# MCU063A_Emulator.net
KiCad netlist of a schematic drawn in Altium Designer
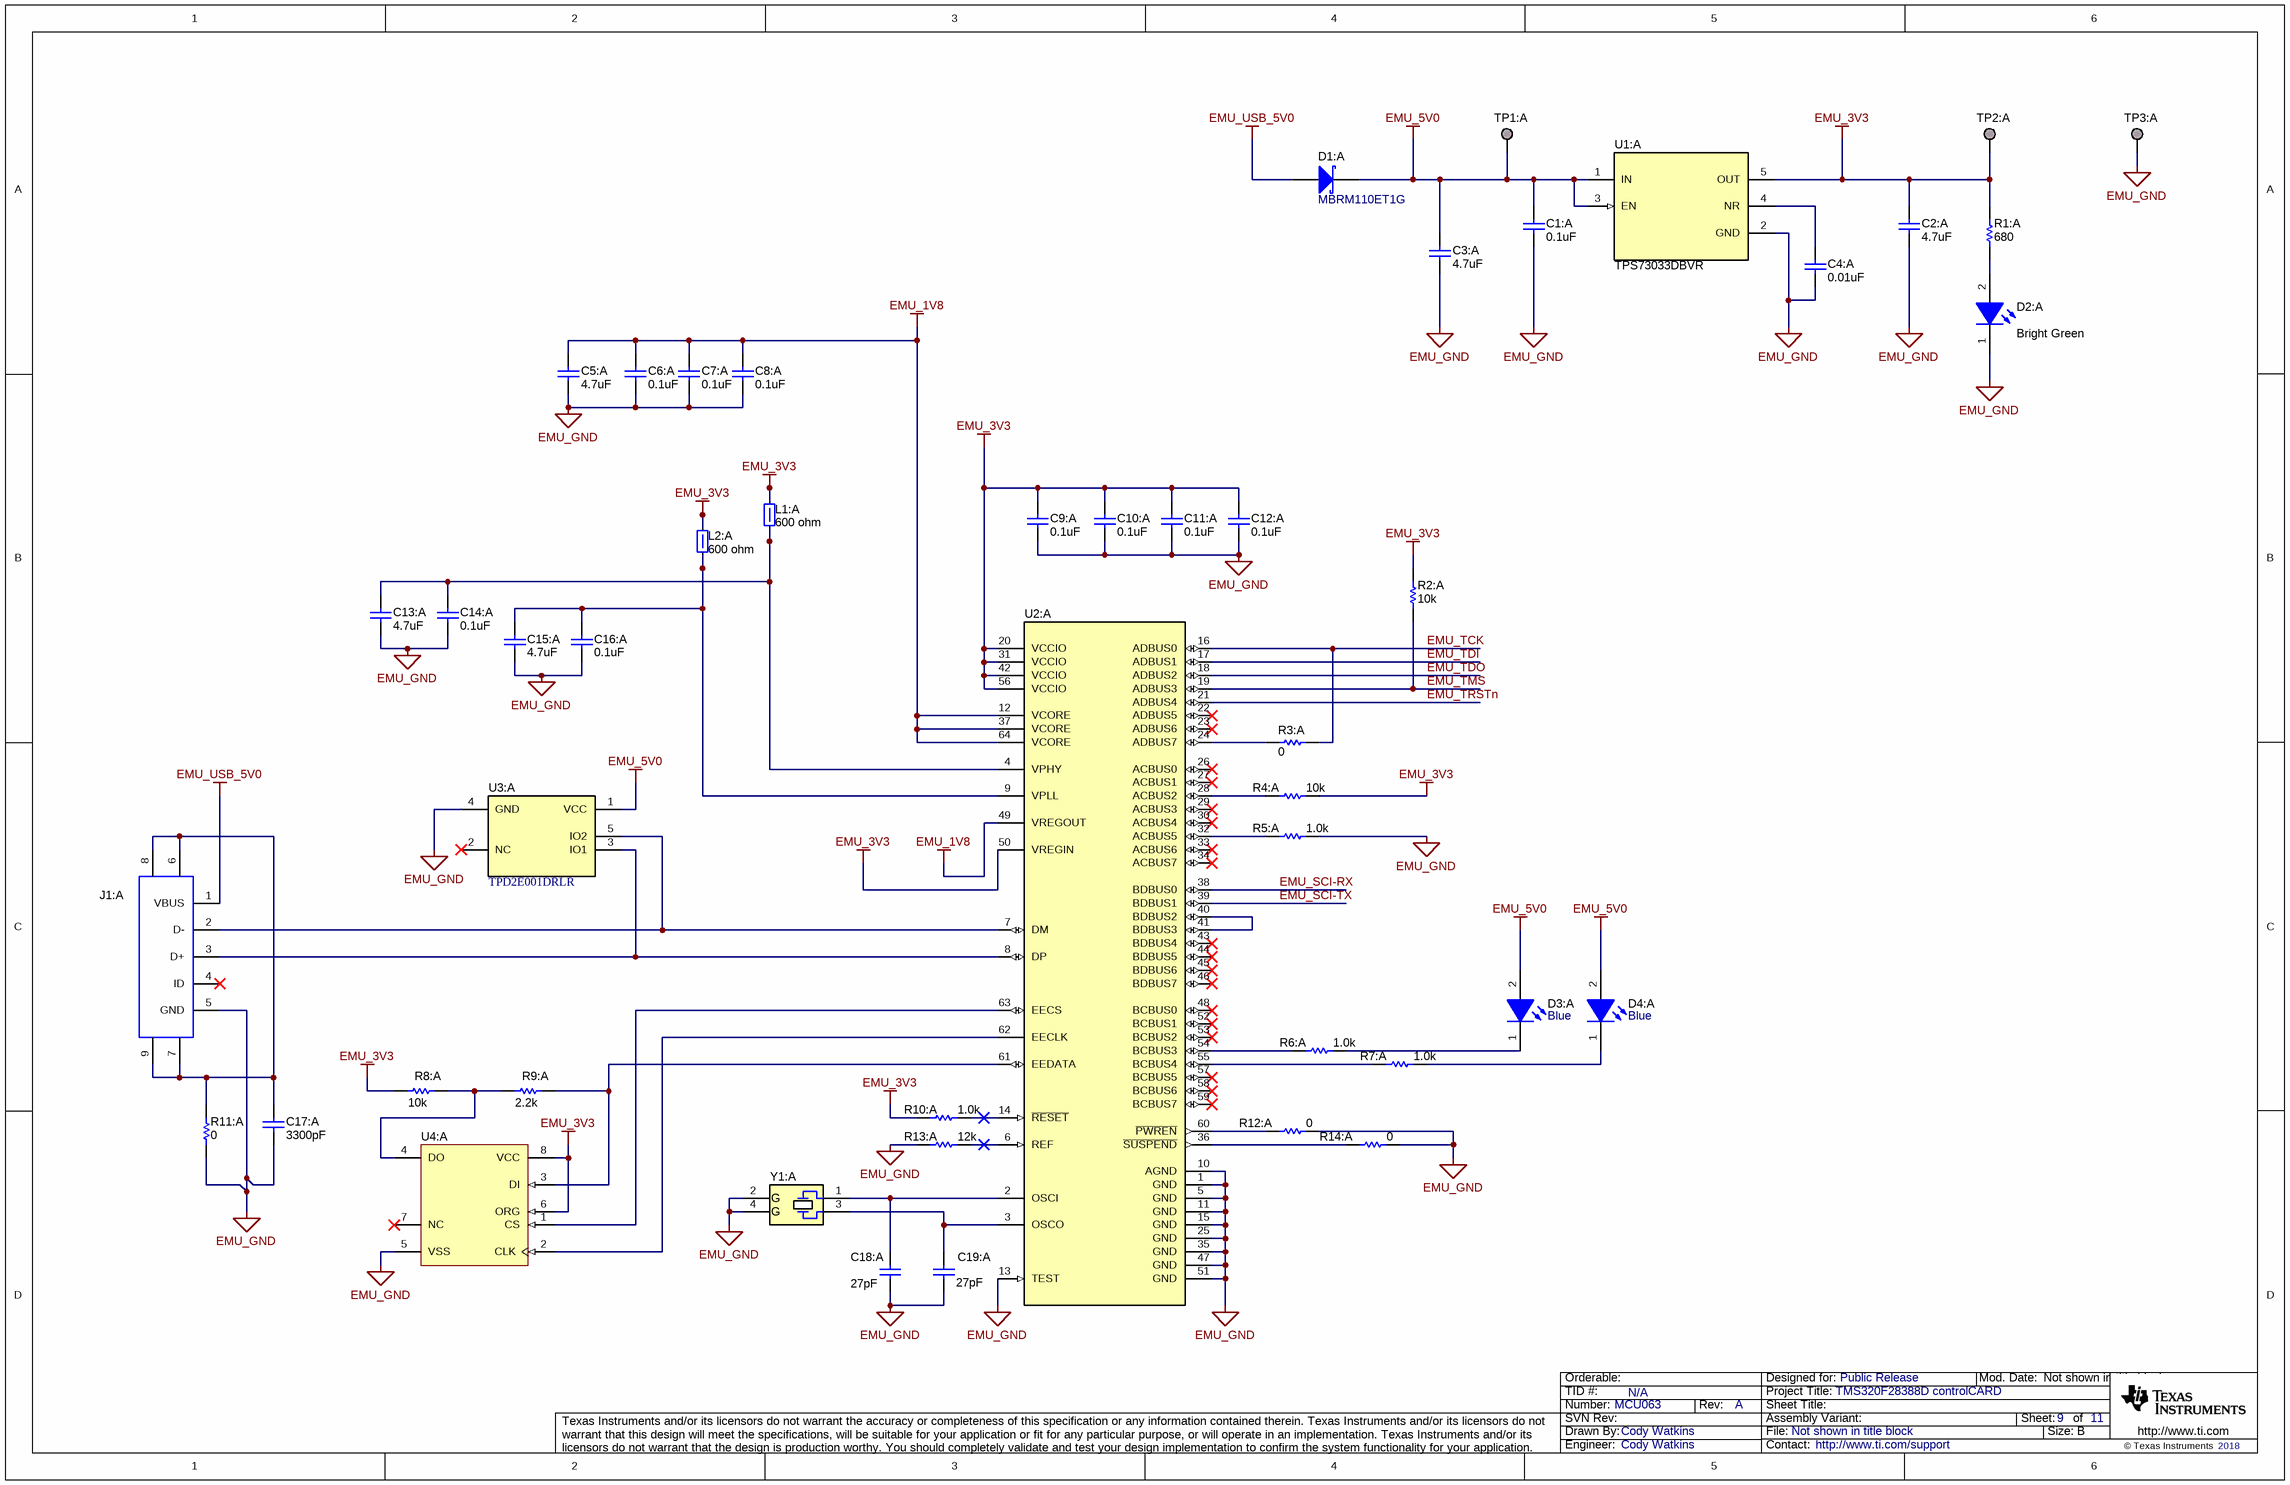
[diagram p0: MCU063A_Emulator.SchDoc]

(export (version "E")
  (design (tool "Eeschema 10.0.6"))
  (components
    (comp (ref "C1:A")
      (value "CL05B104KP5NNNC")
      (footprint "0402")
      (description "CAP, CERM, 0.1 uF, 10 V, +/- 10%, X7R, 0402")
      (fields
        (field (name "VALUEDISPLAYED") "0.1uF")
        (field (name "MANUFACTURER") "Samsung Electro-Mechanics")
        (field (name "PUBLISHER") "Texas Instruments")
      )
      (libsource (lib "Altium Vault - TI") (part "Capacitor"))
    )
    (comp (ref "C2:A")
      (value "C0603C475K9PACTU")
      (footprint "0603")
      (description "CAP, CERM, 4.7 uF, 6.3 V, +/- 10%, X5R, 0603")
      (fields
        (field (name "MANUFACTURER") "Kemet")
        (field (name "VALUEDISPLAYED") "4.7uF")
        (field (name "PUBLISHER") "Texas Instruments")
      )
      (libsource (lib "Altium Vault - TI") (part "Capacitor"))
    )
    (comp (ref "C3:A")
      (value "C0603C475K9PACTU")
      (footprint "0603")
      (description "CAP, CERM, 4.7 uF, 6.3 V, +/- 10%, X5R, 0603")
      (fields
        (field (name "MANUFACTURER") "Kemet")
        (field (name "VALUEDISPLAYED") "4.7uF")
        (field (name "PUBLISHER") "Texas Instruments")
      )
      (libsource (lib "Altium Vault - TI") (part "Capacitor"))
    )
    (comp (ref "C4:A")
      (value "0402ZC103KAT2A")
      (footprint "0402")
      (description "CAP, CERM, 0.01 uF, 10 V, +/- 10%, X7R, 0402")
      (fields
        (field (name "VALUEDISPLAYED") "0.01uF")
        (field (name "MANUFACTURER") "AVX")
        (field (name "PUBLISHER") "Texas Instruments")
      )
      (libsource (lib "Altium Vault - TI") (part "Capacitor"))
    )
    (comp (ref "C5:A")
      (value "C0603C475K9PACTU")
      (footprint "0603")
      (description "CAP, CERM, 4.7 uF, 6.3 V, +/- 10%, X5R, 0603")
      (fields
        (field (name "MANUFACTURER") "Kemet")
        (field (name "VALUEDISPLAYED") "4.7uF")
        (field (name "PUBLISHER") "Texas Instruments")
      )
      (libsource (lib "Altium Vault - TI") (part "Capacitor"))
    )
    (comp (ref "C6:A")
      (value "CL05B104KP5NNNC")
      (footprint "0402")
      (description "CAP, CERM, 0.1 uF, 10 V, +/- 10%, X7R, 0402")
      (fields
        (field (name "VALUEDISPLAYED") "0.1uF")
        (field (name "MANUFACTURER") "Samsung Electro-Mechanics")
        (field (name "PUBLISHER") "Texas Instruments")
      )
      (libsource (lib "Altium Vault - TI") (part "Capacitor"))
    )
    (comp (ref "C7:A")
      (value "CL05B104KP5NNNC")
      (footprint "0402")
      (description "CAP, CERM, 0.1 uF, 10 V, +/- 10%, X7R, 0402")
      (fields
        (field (name "VALUEDISPLAYED") "0.1uF")
        (field (name "MANUFACTURER") "Samsung Electro-Mechanics")
        (field (name "PUBLISHER") "Texas Instruments")
      )
      (libsource (lib "Altium Vault - TI") (part "Capacitor"))
    )
    (comp (ref "C8:A")
      (value "CL05B104KP5NNNC")
      (footprint "0402")
      (description "CAP, CERM, 0.1 uF, 10 V, +/- 10%, X7R, 0402")
      (fields
        (field (name "VALUEDISPLAYED") "0.1uF")
        (field (name "MANUFACTURER") "Samsung Electro-Mechanics")
        (field (name "PUBLISHER") "Texas Instruments")
      )
      (libsource (lib "Altium Vault - TI") (part "Capacitor"))
    )
    (comp (ref "C9:A")
      (value "CL05B104KP5NNNC")
      (footprint "0402")
      (description "CAP, CERM, 0.1 uF, 10 V, +/- 10%, X7R, 0402")
      (fields
        (field (name "VALUEDISPLAYED") "0.1uF")
        (field (name "MANUFACTURER") "Samsung Electro-Mechanics")
        (field (name "PUBLISHER") "Texas Instruments")
      )
      (libsource (lib "Altium Vault - TI") (part "Capacitor"))
    )
    (comp (ref "C10:A")
      (value "CL05B104KP5NNNC")
      (footprint "0402")
      (description "CAP, CERM, 0.1 uF, 10 V, +/- 10%, X7R, 0402")
      (fields
        (field (name "VALUEDISPLAYED") "0.1uF")
        (field (name "MANUFACTURER") "Samsung Electro-Mechanics")
        (field (name "PUBLISHER") "Texas Instruments")
      )
      (libsource (lib "Altium Vault - TI") (part "Capacitor"))
    )
    (comp (ref "C11:A")
      (value "CL05B104KP5NNNC")
      (footprint "0402")
      (description "CAP, CERM, 0.1 uF, 10 V, +/- 10%, X7R, 0402")
      (fields
        (field (name "VALUEDISPLAYED") "0.1uF")
        (field (name "MANUFACTURER") "Samsung Electro-Mechanics")
        (field (name "PUBLISHER") "Texas Instruments")
      )
      (libsource (lib "Altium Vault - TI") (part "Capacitor"))
    )
    (comp (ref "C12:A")
      (value "CL05B104KP5NNNC")
      (footprint "0402")
      (description "CAP, CERM, 0.1 uF, 10 V, +/- 10%, X7R, 0402")
      (fields
        (field (name "VALUEDISPLAYED") "0.1uF")
        (field (name "MANUFACTURER") "Samsung Electro-Mechanics")
        (field (name "PUBLISHER") "Texas Instruments")
      )
      (libsource (lib "Altium Vault - TI") (part "Capacitor"))
    )
    (comp (ref "C13:A")
      (value "C0603C475K9PACTU")
      (footprint "0603")
      (description "CAP, CERM, 4.7 uF, 6.3 V, +/- 10%, X5R, 0603")
      (fields
        (field (name "MANUFACTURER") "Kemet")
        (field (name "VALUEDISPLAYED") "4.7uF")
        (field (name "PUBLISHER") "Texas Instruments")
      )
      (libsource (lib "Altium Vault - TI") (part "Capacitor"))
    )
    (comp (ref "C14:A")
      (value "CL05B104KP5NNNC")
      (footprint "0402")
      (description "CAP, CERM, 0.1 uF, 10 V, +/- 10%, X7R, 0402")
      (fields
        (field (name "VALUEDISPLAYED") "0.1uF")
        (field (name "MANUFACTURER") "Samsung Electro-Mechanics")
        (field (name "PUBLISHER") "Texas Instruments")
      )
      (libsource (lib "Altium Vault - TI") (part "Capacitor"))
    )
    (comp (ref "C15:A")
      (value "C0603C475K9PACTU")
      (footprint "0603")
      (description "CAP, CERM, 4.7 uF, 6.3 V, +/- 10%, X5R, 0603")
      (fields
        (field (name "MANUFACTURER") "Kemet")
        (field (name "VALUEDISPLAYED") "4.7uF")
        (field (name "PUBLISHER") "Texas Instruments")
      )
      (libsource (lib "Altium Vault - TI") (part "Capacitor"))
    )
    (comp (ref "C16:A")
      (value "CL05B104KP5NNNC")
      (footprint "0402")
      (description "CAP, CERM, 0.1 uF, 10 V, +/- 10%, X7R, 0402")
      (fields
        (field (name "VALUEDISPLAYED") "0.1uF")
        (field (name "MANUFACTURER") "Samsung Electro-Mechanics")
        (field (name "PUBLISHER") "Texas Instruments")
      )
      (libsource (lib "Altium Vault - TI") (part "Capacitor"))
    )
    (comp (ref "C17:A")
      (value "CGA2B2X7R1H332K050BA")
      (footprint "0402")
      (description "CAP, CERM, 3300 pF, 50 V, +/- 10%, X7R, AEC-Q200 Grade 1, 0402")
      (fields
        (field (name "MANUFACTURER") "TDK")
        (field (name "VALUEDISPLAYED") "3300pF")
        (field (name "PUBLISHER") "Texas Instruments")
      )
      (libsource (lib "Altium Vault - TI") (part "Capacitor"))
    )
    (comp (ref "C18:A")
      (value "C0402C270J5GACTU")
      (footprint "0402")
      (description "CAP, CERM, 27 pF, 50 V,+/- 5%, C0G/NP0, 0402")
      (fields (field (name "VALUEDISPLAYED") "27pF") (field (name "MANUFACTURER") "Kemet"))
      (libsource (lib "Altium Vault - TI") (part "Capacitor"))
    )
    (comp (ref "C19:A")
      (value "C0402C270J5GACTU")
      (footprint "0402")
      (description "CAP, CERM, 27 pF, 50 V,+/- 5%, C0G/NP0, 0402")
      (fields (field (name "VALUEDISPLAYED") "27pF") (field (name "MANUFACTURER") "Kemet"))
      (libsource (lib "Altium Vault - TI") (part "Capacitor"))
    )
    (comp (ref "D1:A")
      (value "MBRM110ET1G")
      (footprint "POWERMITE")
      (description "Diode, Schottky, 10 V, 1 A, AEC-Q101, POWERMITE")
      (fields (field (name "MANUFACTURER") "ON Semiconductor"))
      (libsource (lib "Altium Vault - TI") (part "DIODE_SCHOTTKY"))
    )
    (comp (ref "D2:A")
      (value "Bright Green")
      (footprint "WL-SMCW_Green_0805")
      (description "LED, Bright Green, SMD")
      (fields
        (field (name "PARTNUMBER") "150080VS75000")
        (field (name "MANUFACTURER") "Wurth Elektronik")
        (field (name "PUBLISHER") "Texas Instruments")
      )
      (libsource (lib "Altium Vault - TI") (part "LED_A2_K1"))
    )
    (comp (ref "D3:A")
      (value "Blue")
      (footprint "WL-SMCW_Blue_0805")
      (description "LED, Blue, SMD")
      (fields (field (name "MANUFACTURER") "Wurth Elektronik") (field (name "PARTNUMBER") "150080BS75000"))
      (libsource (lib "Altium Vault - TI") (part "LED_A2_K1"))
    )
    (comp (ref "D4:A")
      (value "Blue")
      (footprint "WL-SMCW_Blue_0805")
      (description "LED, Blue, SMD")
      (fields (field (name "MANUFACTURER") "Wurth Elektronik") (field (name "PARTNUMBER") "150080BS75000"))
      (libsource (lib "Altium Vault - TI") (part "LED_A2_K1"))
    )
    (comp (ref "J1:A")
      (value "65100516121")
      (footprint "Wurth_65100516121")
      (description "Connector, Receptacle, USB Mini B 2.0, SMT")
      (fields (field (name "MANUFACTURER") "Wurth Elektronik") (field (name "PUBLISHER") "Texas Instruments"))
      (libsource (lib "Altium Vault - TI") (part "CONN_USB_5Pos-4Shld"))
    )
    (comp (ref "L1:A")
      (value "600 ohm")
      (footprint "0805_HV")
      (description "Ferrite Bead, 600 ohm @ 100 MHz, 0.5 A, 0805")
      (fields
        (field (name "PARTNUMBER") "HZ0805E601R-10")
        (field (name "MANUFACTURER") "Laird-Signal Integrity Products")
        (field (name "PUBLISHER") "Texas Instruments")
      )
      (libsource (lib "Altium Vault - TI") (part "Ferrite_Bead"))
    )
    (comp (ref "L2:A")
      (value "600 ohm")
      (footprint "0805_HV")
      (description "Ferrite Bead, 600 ohm @ 100 MHz, 0.5 A, 0805")
      (fields
        (field (name "PARTNUMBER") "HZ0805E601R-10")
        (field (name "MANUFACTURER") "Laird-Signal Integrity Products")
        (field (name "PUBLISHER") "Texas Instruments")
      )
      (libsource (lib "Altium Vault - TI") (part "Ferrite_Bead"))
    )
    (comp (ref "R1:A")
      (value "CRCW0402680RJNED")
      (footprint "0402")
      (description "RES, 680, 5%, 0.063 W, AEC-Q200 Grade 0, 0402")
      (fields (field (name "VALUEDISPLAYED") "680") (field (name "MANUFACTURER") "Vishay-Dale"))
      (libsource (lib "Altium Vault - TI") (part "Resistor"))
    )
    (comp (ref "R2:A")
      (value "CRCW040210K0JNED")
      (footprint "0402")
      (description "RES, 10 k, 5%, 0.063 W, AEC-Q200 Grade 0, 0402")
      (fields (field (name "VALUEDISPLAYED") "10k") (field (name "MANUFACTURER") "Vishay-Dale"))
      (libsource (lib "Altium Vault - TI") (part "Resistor"))
    )
    (comp (ref "R3:A")
      (value "CRCW04020000Z0ED")
      (footprint "0402")
      (description "RES, 0, 5%, 0.063 W, AEC-Q200 Grade 0, 0402")
      (fields (field (name "VALUEDISPLAYED") "0") (field (name "MANUFACTURER") "Vishay-Dale"))
      (libsource (lib "Altium Vault - TI") (part "Resistor"))
    )
    (comp (ref "R4:A")
      (value "CRCW040210K0JNED")
      (footprint "0402")
      (description "RES, 10 k, 5%, 0.063 W, AEC-Q200 Grade 0, 0402")
      (fields (field (name "VALUEDISPLAYED") "10k") (field (name "MANUFACTURER") "Vishay-Dale"))
      (libsource (lib "Altium Vault - TI") (part "Resistor"))
    )
    (comp (ref "R5:A")
      (value "CRCW04021K00JNED")
      (footprint "0402")
      (description "RES, 1.0 k, 5%, 0.063 W, AEC-Q200 Grade 0, 0402")
      (fields (field (name "VALUEDISPLAYED") "1.0k") (field (name "MANUFACTURER") "Vishay-Dale"))
      (libsource (lib "Altium Vault - TI") (part "Resistor"))
    )
    (comp (ref "R6:A")
      (value "CRCW04021K00JNED")
      (footprint "0402")
      (description "RES, 1.0 k, 5%, 0.063 W, AEC-Q200 Grade 0, 0402")
      (fields (field (name "VALUEDISPLAYED") "1.0k") (field (name "MANUFACTURER") "Vishay-Dale"))
      (libsource (lib "Altium Vault - TI") (part "Resistor"))
    )
    (comp (ref "R7:A")
      (value "CRCW04021K00JNED")
      (footprint "0402")
      (description "RES, 1.0 k, 5%, 0.063 W, AEC-Q200 Grade 0, 0402")
      (fields (field (name "VALUEDISPLAYED") "1.0k") (field (name "MANUFACTURER") "Vishay-Dale"))
      (libsource (lib "Altium Vault - TI") (part "Resistor"))
    )
    (comp (ref "R8:A")
      (value "CRCW040210K0JNED")
      (footprint "0402")
      (description "RES, 10 k, 5%, 0.063 W, AEC-Q200 Grade 0, 0402")
      (fields (field (name "VALUEDISPLAYED") "10k") (field (name "MANUFACTURER") "Vishay-Dale"))
      (libsource (lib "Altium Vault - TI") (part "Resistor"))
    )
    (comp (ref "R9:A")
      (value "CRCW04022K20JNED")
      (footprint "0402")
      (description "RES, 2.2 k, 5%, 0.063 W, AEC-Q200 Grade 0, 0402")
      (fields (field (name "VALUEDISPLAYED") "2.2k") (field (name "MANUFACTURER") "Vishay-Dale"))
      (libsource (lib "Altium Vault - TI") (part "Resistor"))
    )
    (comp (ref "R10:A")
      (value "CRCW04021K00JNED")
      (footprint "0402")
      (description "RES, 1.0 k, 5%, 0.063 W, AEC-Q200 Grade 0, 0402")
      (fields (field (name "VALUEDISPLAYED") "1.0k") (field (name "MANUFACTURER") "Vishay-Dale"))
      (libsource (lib "Altium Vault - TI") (part "Resistor"))
    )
    (comp (ref "R11:A")
      (value "CRCW04020000Z0ED")
      (footprint "0402")
      (description "RES, 0, 5%, 0.063 W, AEC-Q200 Grade 0, 0402")
      (fields (field (name "VALUEDISPLAYED") "0") (field (name "MANUFACTURER") "Vishay-Dale"))
      (libsource (lib "Altium Vault - TI") (part "Resistor"))
    )
    (comp (ref "R12:A")
      (value "CRCW04020000Z0ED")
      (footprint "0402")
      (description "RES, 0, 5%, 0.063 W, AEC-Q200 Grade 0, 0402")
      (fields (field (name "VALUEDISPLAYED") "0") (field (name "MANUFACTURER") "Vishay-Dale"))
      (libsource (lib "Altium Vault - TI") (part "Resistor"))
    )
    (comp (ref "R13:A")
      (value "CRCW040212K0JNED")
      (footprint "0402")
      (description "RES, 12 k, 5%, 0.063 W, AEC-Q200 Grade 0, 0402")
      (fields (field (name "VALUEDISPLAYED") "12k") (field (name "MANUFACTURER") "Vishay-Dale"))
      (libsource (lib "Altium Vault - TI") (part "Resistor"))
    )
    (comp (ref "R14:A")
      (value "CRCW04020000Z0ED")
      (footprint "0402")
      (description "RES, 0, 5%, 0.063 W, AEC-Q200 Grade 0, 0402")
      (fields (field (name "VALUEDISPLAYED") "0") (field (name "MANUFACTURER") "Vishay-Dale"))
      (libsource (lib "Altium Vault - TI") (part "Resistor"))
    )
    (comp (ref "TP1:A")
      (value "TESTPOINT")
      (footprint "TP_50MIL-25MILHOLE")
      (description "TEST POINT.  No entry in BOM.")
      (libsource (lib "Altium Vault - TI") (part "CMP-0078143-2"))
    )
    (comp (ref "TP2:A")
      (value "TESTPOINT")
      (footprint "TP_50MIL-25MILHOLE")
      (description "TEST POINT.  No entry in BOM.")
      (libsource (lib "Altium Vault - TI") (part "CMP-0078143-2"))
    )
    (comp (ref "TP3:A")
      (value "TESTPOINT")
      (footprint "TP_50MIL-25MILHOLE")
      (description "TEST POINT.  No entry in BOM.")
      (libsource (lib "Altium Vault - TI") (part "CMP-0078143-2"))
    )
    (comp (ref "U1:A")
      (value "TPS73033DBVR")
      (footprint "DBV0005A_N")
      (description "Low-Noise, High PSRR, RF 200-mA Low-Dropout Linear Regulators, DBV0005A (SOT-23-5)")
      (fields
        (field (name "ALTERNATE PARTNUMBER") "TPS73033DBVT")
        (field (name "MANUFACTURER") "Texas Instruments")
        (field (name "PUBLISHER") "Texas Instruments")
      )
      (libsource (lib "Altium Vault - TI") (part "TPS730XXDBV"))
    )
    (comp (ref "U2:A")
      (value "FT2232HL-REEL")
      (footprint "LQFP64_N")
      (description "Dual High Speed USB To Multipurpose UART/FIFO IC, LQFP-64")
      (fields (field (name "MANUFACTURER") "FTDI") (field (name "PUBLISHER") "Texas Instruments"))
      (libsource (lib "Altium Vault - TI") (part "CMP-0004796-1"))
    )
    (comp (ref "U3:A")
      (value "TPD2E001DRLR")
      (footprint "DRL0005A")
      (fields (field (name "MANUFACTURER") "Texas Instruments"))
      (libsource (lib "Altium Vault - TI") (part "TI-TPD2E001-Q1-SOT_DRL-5"))
    )
    (comp (ref "U4:A")
      (value "93LC56C-I/SN")
      (footprint "SOIC-8")
      (description "2K Microwire Compatible Serial EEPROM, SOIC-8")
      (fields (field (name "MANUFACTURER") "Microchip") (field (name "PUBLISHER") "Texas Instruments"))
      (libsource (lib "Altium Vault - TI") (part "93LC46C-SN"))
    )
    (comp (ref "Y1:A")
      (value "ECS-120-20-30B-TR")
      (footprint "ECS_ECX-53B")
      (description "Crystal, 12 MHz, 20pF, SMD")
      (fields (field (name "MANUFACTURER") "ECS Inc."))
      (libsource (lib "Altium Vault - TI") (part "CMP-0004646-3"))
    )
  )
  (nets
    (net (code "1") (name "/EMU_SCI-RX") (class "Default")
      (node (ref "U2:A") (pin "38") (pinfunction "BDBUS0_38") (pintype "bidirectional"))
    )
    (net (code "2") (name "/EMU_SCI-TX") (class "Default")
      (node (ref "U2:A") (pin "39") (pinfunction "BDBUS1_39") (pintype "bidirectional"))
    )
    (net (code "3") (name "/EMU_TCK") (class "Default")
      (node (ref "R3:A") (pin "1") (pinfunction "1_1") (pintype "passive"))
      (node (ref "U2:A") (pin "16") (pinfunction "ADBUS0_16") (pintype "bidirectional"))
    )
    (net (code "4") (name "/EMU_TDI") (class "Default")
      (node (ref "U2:A") (pin "17") (pinfunction "ADBUS1_17") (pintype "bidirectional"))
    )
    (net (code "5") (name "/EMU_TDO") (class "Default")
      (node (ref "U2:A") (pin "18") (pinfunction "ADBUS2_18") (pintype "bidirectional"))
    )
    (net (code "6") (name "/EMU_TMS") (class "Default")
      (node (ref "R2:A") (pin "1") (pinfunction "1_1") (pintype "passive"))
      (node (ref "U2:A") (pin "19") (pinfunction "ADBUS3_19") (pintype "bidirectional"))
    )
    (net (code "7") (name "/EMU_TRSTn") (class "Default")
      (node (ref "U2:A") (pin "21") (pinfunction "ADBUS4_21") (pintype "bidirectional"))
    )
    (net (code "8") (name "EMU_1V8") (class "Default")
      (node (ref "C5:A") (pin "2") (pinfunction "2_2") (pintype "passive"))
      (node (ref "C6:A") (pin "2") (pinfunction "2_2") (pintype "passive"))
      (node (ref "C7:A") (pin "2") (pinfunction "2_2") (pintype "passive"))
      (node (ref "C8:A") (pin "2") (pinfunction "2_2") (pintype "passive"))
      (node (ref "U2:A") (pin "12") (pinfunction "VCORE_12") (pintype "power_in"))
      (node (ref "U2:A") (pin "37") (pinfunction "VCORE_37") (pintype "power_in"))
      (node (ref "U2:A") (pin "49") (pinfunction "VREGOUT_49") (pintype "power_in"))
      (node (ref "U2:A") (pin "64") (pinfunction "VCORE_64") (pintype "power_in"))
    )
    (net (code "9") (name "EMU_3V3") (class "Default")
      (node (ref "C10:A") (pin "2") (pinfunction "2_2") (pintype "passive"))
      (node (ref "C11:A") (pin "2") (pinfunction "2_2") (pintype "passive"))
      (node (ref "C12:A") (pin "2") (pinfunction "2_2") (pintype "passive"))
      (node (ref "C2:A") (pin "1") (pinfunction "1_1") (pintype "passive"))
      (node (ref "C9:A") (pin "2") (pinfunction "2_2") (pintype "passive"))
      (node (ref "L1:A") (pin "2") (pinfunction "2_2") (pintype "passive"))
      (node (ref "L2:A") (pin "2") (pinfunction "2_2") (pintype "passive"))
      (node (ref "R10:A") (pin "1") (pinfunction "1_1") (pintype "passive"))
      (node (ref "R1:A") (pin "1") (pinfunction "1_1") (pintype "passive"))
      (node (ref "R2:A") (pin "2") (pinfunction "2_2") (pintype "passive"))
      (node (ref "R4:A") (pin "2") (pinfunction "2_2") (pintype "passive"))
      (node (ref "R8:A") (pin "1") (pinfunction "1_1") (pintype "passive"))
      (node (ref "TP2:A") (pin "1") (pintype "passive"))
      (node (ref "U1:A") (pin "5") (pinfunction "OUT_5") (pintype "power_in"))
      (node (ref "U2:A") (pin "20") (pinfunction "VCCIO_20") (pintype "power_in"))
      (node (ref "U2:A") (pin "31") (pinfunction "VCCIO_31") (pintype "power_in"))
      (node (ref "U2:A") (pin "42") (pinfunction "VCCIO_42") (pintype "power_in"))
      (node (ref "U2:A") (pin "50") (pinfunction "VREGIN_50") (pintype "power_in"))
      (node (ref "U2:A") (pin "56") (pinfunction "VCCIO_56") (pintype "power_in"))
      (node (ref "U4:A") (pin "6") (pinfunction "ORG_6") (pintype "input"))
      (node (ref "U4:A") (pin "8") (pinfunction "VCC_8") (pintype "power_in"))
    )
    (net (code "10") (name "EMU_5V0") (class "Default")
      (node (ref "C1:A") (pin "2") (pinfunction "2_2") (pintype "passive"))
      (node (ref "C3:A") (pin "1") (pinfunction "1_1") (pintype "passive"))
      (node (ref "D1:A") (pin "1") (pinfunction "K_1") (pintype "passive"))
      (node (ref "D3:A") (pin "2") (pinfunction "A_2") (pintype "passive"))
      (node (ref "D4:A") (pin "2") (pinfunction "A_2") (pintype "passive"))
      (node (ref "TP1:A") (pin "1") (pintype "passive"))
      (node (ref "U1:A") (pin "1") (pinfunction "IN_1") (pintype "power_in"))
      (node (ref "U1:A") (pin "3") (pinfunction "EN_3") (pintype "input"))
      (node (ref "U3:A") (pin "1") (pinfunction "VCC_1") (pintype "power_in"))
    )
    (net (code "11") (name "EMU_GND") (class "Default")
      (node (ref "C10:A") (pin "1") (pinfunction "1_1") (pintype "passive"))
      (node (ref "C11:A") (pin "1") (pinfunction "1_1") (pintype "passive"))
      (node (ref "C12:A") (pin "1") (pinfunction "1_1") (pintype "passive"))
      (node (ref "C13:A") (pin "2") (pinfunction "2_2") (pintype "passive"))
      (node (ref "C14:A") (pin "1") (pinfunction "1_1") (pintype "passive"))
      (node (ref "C15:A") (pin "2") (pinfunction "2_2") (pintype "passive"))
      (node (ref "C16:A") (pin "1") (pinfunction "1_1") (pintype "passive"))
      (node (ref "C17:A") (pin "1") (pinfunction "1_1") (pintype "passive"))
      (node (ref "C18:A") (pin "1") (pinfunction "1_1") (pintype "passive"))
      (node (ref "C19:A") (pin "1") (pinfunction "1_1") (pintype "passive"))
      (node (ref "C1:A") (pin "1") (pinfunction "1_1") (pintype "passive"))
      (node (ref "C2:A") (pin "2") (pinfunction "2_2") (pintype "passive"))
      (node (ref "C3:A") (pin "2") (pinfunction "2_2") (pintype "passive"))
      (node (ref "C4:A") (pin "1") (pinfunction "1_1") (pintype "passive"))
      (node (ref "C5:A") (pin "1") (pinfunction "1_1") (pintype "passive"))
      (node (ref "C6:A") (pin "1") (pinfunction "1_1") (pintype "passive"))
      (node (ref "C7:A") (pin "1") (pinfunction "1_1") (pintype "passive"))
      (node (ref "C8:A") (pin "1") (pinfunction "1_1") (pintype "passive"))
      (node (ref "C9:A") (pin "1") (pinfunction "1_1") (pintype "passive"))
      (node (ref "D2:A") (pin "1") (pinfunction "K_1") (pintype "passive"))
      (node (ref "J1:A") (pin "5") (pinfunction "GND_5") (pintype "passive"))
      (node (ref "R11:A") (pin "2") (pinfunction "2_2") (pintype "passive"))
      (node (ref "R12:A") (pin "1") (pinfunction "1_1") (pintype "passive"))
      (node (ref "R13:A") (pin "1") (pinfunction "1_1") (pintype "passive"))
      (node (ref "R14:A") (pin "1") (pinfunction "1_1") (pintype "passive"))
      (node (ref "R5:A") (pin "2") (pinfunction "2_2") (pintype "passive"))
      (node (ref "TP3:A") (pin "1") (pintype "passive"))
      (node (ref "U1:A") (pin "2") (pinfunction "GND_2") (pintype "power_in"))
      (node (ref "U2:A") (pin "1") (pinfunction "GND_1") (pintype "power_in"))
      (node (ref "U2:A") (pin "10") (pinfunction "AGND_10") (pintype "power_in"))
      (node (ref "U2:A") (pin "11") (pinfunction "GND_11") (pintype "power_in"))
      (node (ref "U2:A") (pin "13") (pinfunction "TEST_13") (pintype "input"))
      (node (ref "U2:A") (pin "15") (pinfunction "GND_15") (pintype "power_in"))
      (node (ref "U2:A") (pin "25") (pinfunction "GND_25") (pintype "power_in"))
      (node (ref "U2:A") (pin "35") (pinfunction "GND_35") (pintype "power_in"))
      (node (ref "U2:A") (pin "47") (pinfunction "GND_47") (pintype "power_in"))
      (node (ref "U2:A") (pin "5") (pinfunction "GND_5") (pintype "power_in"))
      (node (ref "U2:A") (pin "51") (pinfunction "GND_51") (pintype "power_in"))
      (node (ref "U3:A") (pin "4") (pinfunction "GND_4") (pintype "power_in"))
      (node (ref "U4:A") (pin "5") (pinfunction "VSS_5") (pintype "power_in"))
      (node (ref "Y1:A") (pin "2") (pinfunction "GND_2") (pintype "power_in"))
      (node (ref "Y1:A") (pin "4") (pinfunction "GND_4") (pintype "power_in"))
    )
    (net (code "12") (name "EMU_USB_5V0") (class "Default")
      (node (ref "D1:A") (pin "2") (pinfunction "A_2") (pintype "passive"))
      (node (ref "J1:A") (pin "1") (pinfunction "VBUS_1") (pintype "passive"))
    )
    (net (code "13") (name "Net-(C17:A-Pad2)") (class "Default")
      (node (ref "C17:A") (pin "2") (pinfunction "2_2") (pintype "passive"))
      (node (ref "J1:A") (pin "6") (pinfunction "6_6") (pintype "passive"))
      (node (ref "J1:A") (pin "7") (pinfunction "7_7") (pintype "passive"))
      (node (ref "J1:A") (pin "8") (pinfunction "8_8") (pintype "passive"))
      (node (ref "J1:A") (pin "9") (pinfunction "9_9") (pintype "passive"))
      (node (ref "R11:A") (pin "1") (pinfunction "1_1") (pintype "passive"))
    )
    (net (code "14") (name "Net-(D2:A-A)") (class "Default")
      (node (ref "D2:A") (pin "2") (pinfunction "A_2") (pintype "passive"))
      (node (ref "R1:A") (pin "2") (pinfunction "2_2") (pintype "passive"))
    )
    (net (code "15") (name "Net-(D3:A-K)") (class "Default")
      (node (ref "D3:A") (pin "1") (pinfunction "K_1") (pintype "passive"))
      (node (ref "R6:A") (pin "2") (pinfunction "2_2") (pintype "passive"))
    )
    (net (code "16") (name "Net-(D4:A-K)") (class "Default")
      (node (ref "D4:A") (pin "1") (pinfunction "K_1") (pintype "passive"))
      (node (ref "R7:A") (pin "2") (pinfunction "2_2") (pintype "passive"))
    )
    (net (code "17") (name "Net-(J1:A-D+)") (class "Default")
      (node (ref "J1:A") (pin "3") (pinfunction "D+_3") (pintype "passive"))
      (node (ref "U2:A") (pin "8") (pinfunction "DP_8") (pintype "bidirectional"))
      (node (ref "U3:A") (pin "3") (pinfunction "IO1_3") (pintype "passive"))
    )
    (net (code "18") (name "Net-(J1:A-D-)") (class "Default")
      (node (ref "J1:A") (pin "2") (pinfunction "D-_2") (pintype "passive"))
      (node (ref "U2:A") (pin "7") (pinfunction "DM_7") (pintype "bidirectional"))
      (node (ref "U3:A") (pin "5") (pinfunction "IO2_5") (pintype "passive"))
    )
    (net (code "19") (name "Net-(U1:A-NR)") (class "Default")
      (node (ref "C4:A") (pin "2") (pinfunction "2_2") (pintype "passive"))
      (node (ref "U1:A") (pin "4") (pinfunction "NR_4") (pintype "passive"))
    )
    (net (code "20") (name "Net-(U2:A-ACBUS2)") (class "Default")
      (node (ref "R4:A") (pin "1") (pinfunction "1_1") (pintype "passive"))
      (node (ref "U2:A") (pin "28") (pinfunction "ACBUS2_28") (pintype "bidirectional"))
    )
    (net (code "21") (name "Net-(U2:A-ACBUS5)") (class "Default")
      (node (ref "R5:A") (pin "1") (pinfunction "1_1") (pintype "passive"))
      (node (ref "U2:A") (pin "32") (pinfunction "ACBUS5_32") (pintype "bidirectional"))
    )
    (net (code "22") (name "Net-(U2:A-ADBUS7)") (class "Default")
      (node (ref "R3:A") (pin "2") (pinfunction "2_2") (pintype "passive"))
      (node (ref "U2:A") (pin "24") (pinfunction "ADBUS7_24") (pintype "bidirectional"))
    )
    (net (code "23") (name "Net-(U2:A-BCBUS3)") (class "Default")
      (node (ref "R6:A") (pin "1") (pinfunction "1_1") (pintype "passive"))
      (node (ref "U2:A") (pin "54") (pinfunction "BCBUS3_54") (pintype "bidirectional"))
    )
    (net (code "24") (name "Net-(U2:A-BCBUS4)") (class "Default")
      (node (ref "R7:A") (pin "1") (pinfunction "1_1") (pintype "passive"))
      (node (ref "U2:A") (pin "55") (pinfunction "BCBUS4_55") (pintype "bidirectional"))
    )
    (net (code "25") (name "Net-(U2:A-BDBUS2)") (class "Default")
      (node (ref "U2:A") (pin "40") (pinfunction "BDBUS2_40") (pintype "bidirectional"))
      (node (ref "U2:A") (pin "41") (pinfunction "BDBUS3_41") (pintype "bidirectional"))
    )
    (net (code "26") (name "Net-(U2:A-EECLK)") (class "Default")
      (node (ref "U2:A") (pin "62") (pinfunction "EECLK_62") (pintype "tri_state"))
      (node (ref "U4:A") (pin "2") (pinfunction "CLK_2") (pintype "input"))
    )
    (net (code "27") (name "Net-(U2:A-EECS)") (class "Default")
      (node (ref "U2:A") (pin "63") (pinfunction "EECS_63") (pintype "bidirectional"))
      (node (ref "U4:A") (pin "1") (pinfunction "CS_1") (pintype "input"))
    )
    (net (code "28") (name "Net-(U2:A-EEDATA)") (class "Default")
      (node (ref "R9:A") (pin "2") (pinfunction "2_2") (pintype "passive"))
      (node (ref "U2:A") (pin "61") (pinfunction "EEDATA_61") (pintype "bidirectional"))
      (node (ref "U4:A") (pin "3") (pinfunction "DI_3") (pintype "input"))
    )
    (net (code "29") (name "Net-(U2:A-OSCI)") (class "Default")
      (node (ref "C18:A") (pin "2") (pinfunction "2_2") (pintype "passive"))
      (node (ref "U2:A") (pin "2") (pinfunction "OSCI_2") (pintype "passive"))
      (node (ref "Y1:A") (pin "1") (pinfunction "1_1") (pintype "passive"))
    )
    (net (code "30") (name "Net-(U2:A-OSCO)") (class "Default")
      (node (ref "C19:A") (pin "2") (pinfunction "2_2") (pintype "passive"))
      (node (ref "U2:A") (pin "3") (pinfunction "OSCO_3") (pintype "passive"))
      (node (ref "Y1:A") (pin "3") (pinfunction "3_3") (pintype "passive"))
    )
    (net (code "31") (name "Net-(U2:A-REF)") (class "Default")
      (node (ref "R13:A") (pin "2") (pinfunction "2_2") (pintype "passive"))
      (node (ref "U2:A") (pin "6") (pinfunction "REF_6") (pintype "input"))
    )
    (net (code "32") (name "Net-(U2:A-VPHY)") (class "Default")
      (node (ref "C13:A") (pin "1") (pinfunction "1_1") (pintype "passive"))
      (node (ref "C14:A") (pin "2") (pinfunction "2_2") (pintype "passive"))
      (node (ref "L1:A") (pin "1") (pinfunction "1_1") (pintype "passive"))
      (node (ref "U2:A") (pin "4") (pinfunction "VPHY_4") (pintype "power_in"))
    )
    (net (code "33") (name "Net-(U2:A-VPLL)") (class "Default")
      (node (ref "C15:A") (pin "1") (pinfunction "1_1") (pintype "passive"))
      (node (ref "C16:A") (pin "2") (pinfunction "2_2") (pintype "passive"))
      (node (ref "L2:A") (pin "1") (pinfunction "1_1") (pintype "passive"))
      (node (ref "U2:A") (pin "9") (pinfunction "VPLL_9") (pintype "power_in"))
    )
    (net (code "34") (name "Net-(U2:A-~{PWREN})") (class "Default")
      (node (ref "R12:A") (pin "2") (pinfunction "2_2") (pintype "passive"))
      (node (ref "U2:A") (pin "60") (pinfunction "~{PWREN}_60") (pintype "output"))
    )
    (net (code "35") (name "Net-(U2:A-~{RESET})") (class "Default")
      (node (ref "R10:A") (pin "2") (pinfunction "2_2") (pintype "passive"))
      (node (ref "U2:A") (pin "14") (pinfunction "~{RESET}_14") (pintype "input"))
    )
    (net (code "36") (name "Net-(U2:A-~{SUSPEND})") (class "Default")
      (node (ref "R14:A") (pin "2") (pinfunction "2_2") (pintype "passive"))
      (node (ref "U2:A") (pin "36") (pinfunction "~{SUSPEND}_36") (pintype "output"))
    )
    (net (code "37") (name "Net-(U4:A-DO)") (class "Default")
      (node (ref "R8:A") (pin "2") (pinfunction "2_2") (pintype "passive"))
      (node (ref "R9:A") (pin "1") (pinfunction "1_1") (pintype "passive"))
      (node (ref "U4:A") (pin "4") (pinfunction "DO_4") (pintype "tri_state"))
    )
    (net (code "38") (name "unconnected-(J1:A-ID-Pad4)") (class "Default")
      (node (ref "J1:A") (pin "4") (pinfunction "ID_4") (pintype "passive+no_connect"))
    )
    (net (code "39") (name "unconnected-(U2:A-ACBUS0-Pad26)") (class "Default")
      (node (ref "U2:A") (pin "26") (pinfunction "ACBUS0_26") (pintype "bidirectional+no_connect"))
    )
    (net (code "40") (name "unconnected-(U2:A-ACBUS1-Pad27)") (class "Default")
      (node (ref "U2:A") (pin "27") (pinfunction "ACBUS1_27") (pintype "bidirectional+no_connect"))
    )
    (net (code "41") (name "unconnected-(U2:A-ACBUS3-Pad29)") (class "Default")
      (node (ref "U2:A") (pin "29") (pinfunction "ACBUS3_29") (pintype "bidirectional+no_connect"))
    )
    (net (code "42") (name "unconnected-(U2:A-ACBUS4-Pad30)") (class "Default")
      (node (ref "U2:A") (pin "30") (pinfunction "ACBUS4_30") (pintype "bidirectional+no_connect"))
    )
    (net (code "43") (name "unconnected-(U2:A-ACBUS6-Pad33)") (class "Default")
      (node (ref "U2:A") (pin "33") (pinfunction "ACBUS6_33") (pintype "bidirectional+no_connect"))
    )
    (net (code "44") (name "unconnected-(U2:A-ACBUS7-Pad34)") (class "Default")
      (node (ref "U2:A") (pin "34") (pinfunction "ACBUS7_34") (pintype "bidirectional+no_connect"))
    )
    (net (code "45") (name "unconnected-(U2:A-ADBUS5-Pad22)") (class "Default")
      (node (ref "U2:A") (pin "22") (pinfunction "ADBUS5_22") (pintype "bidirectional+no_connect"))
    )
    (net (code "46") (name "unconnected-(U2:A-ADBUS6-Pad23)") (class "Default")
      (node (ref "U2:A") (pin "23") (pinfunction "ADBUS6_23") (pintype "bidirectional+no_connect"))
    )
    (net (code "47") (name "unconnected-(U2:A-BCBUS0-Pad48)") (class "Default")
      (node (ref "U2:A") (pin "48") (pinfunction "BCBUS0_48") (pintype "bidirectional+no_connect"))
    )
    (net (code "48") (name "unconnected-(U2:A-BCBUS1-Pad52)") (class "Default")
      (node (ref "U2:A") (pin "52") (pinfunction "BCBUS1_52") (pintype "bidirectional+no_connect"))
    )
    (net (code "49") (name "unconnected-(U2:A-BCBUS2-Pad53)") (class "Default")
      (node (ref "U2:A") (pin "53") (pinfunction "BCBUS2_53") (pintype "bidirectional+no_connect"))
    )
    (net (code "50") (name "unconnected-(U2:A-BCBUS5-Pad57)") (class "Default")
      (node (ref "U2:A") (pin "57") (pinfunction "BCBUS5_57") (pintype "bidirectional+no_connect"))
    )
    (net (code "51") (name "unconnected-(U2:A-BCBUS6-Pad58)") (class "Default")
      (node (ref "U2:A") (pin "58") (pinfunction "BCBUS6_58") (pintype "bidirectional+no_connect"))
    )
    (net (code "52") (name "unconnected-(U2:A-BCBUS7-Pad59)") (class "Default")
      (node (ref "U2:A") (pin "59") (pinfunction "BCBUS7_59") (pintype "bidirectional+no_connect"))
    )
    (net (code "53") (name "unconnected-(U2:A-BDBUS4-Pad43)") (class "Default")
      (node (ref "U2:A") (pin "43") (pinfunction "BDBUS4_43") (pintype "bidirectional+no_connect"))
    )
    (net (code "54") (name "unconnected-(U2:A-BDBUS5-Pad44)") (class "Default")
      (node (ref "U2:A") (pin "44") (pinfunction "BDBUS5_44") (pintype "bidirectional+no_connect"))
    )
    (net (code "55") (name "unconnected-(U2:A-BDBUS6-Pad45)") (class "Default")
      (node (ref "U2:A") (pin "45") (pinfunction "BDBUS6_45") (pintype "bidirectional+no_connect"))
    )
    (net (code "56") (name "unconnected-(U2:A-BDBUS7-Pad46)") (class "Default")
      (node (ref "U2:A") (pin "46") (pinfunction "BDBUS7_46") (pintype "bidirectional+no_connect"))
    )
    (net (code "57") (name "unconnected-(U3:A-NC-Pad2)") (class "Default")
      (node (ref "U3:A") (pin "2") (pinfunction "NC_2") (pintype "passive+no_connect"))
    )
    (net (code "58") (name "unconnected-(U4:A-NC-Pad7)") (class "Default")
      (node (ref "U4:A") (pin "7") (pinfunction "NC_7") (pintype "passive+no_connect"))
    )
  )
)
